# pic16f1508_breakout.net
KiCad netlist of a schematic drawn in EAGLE
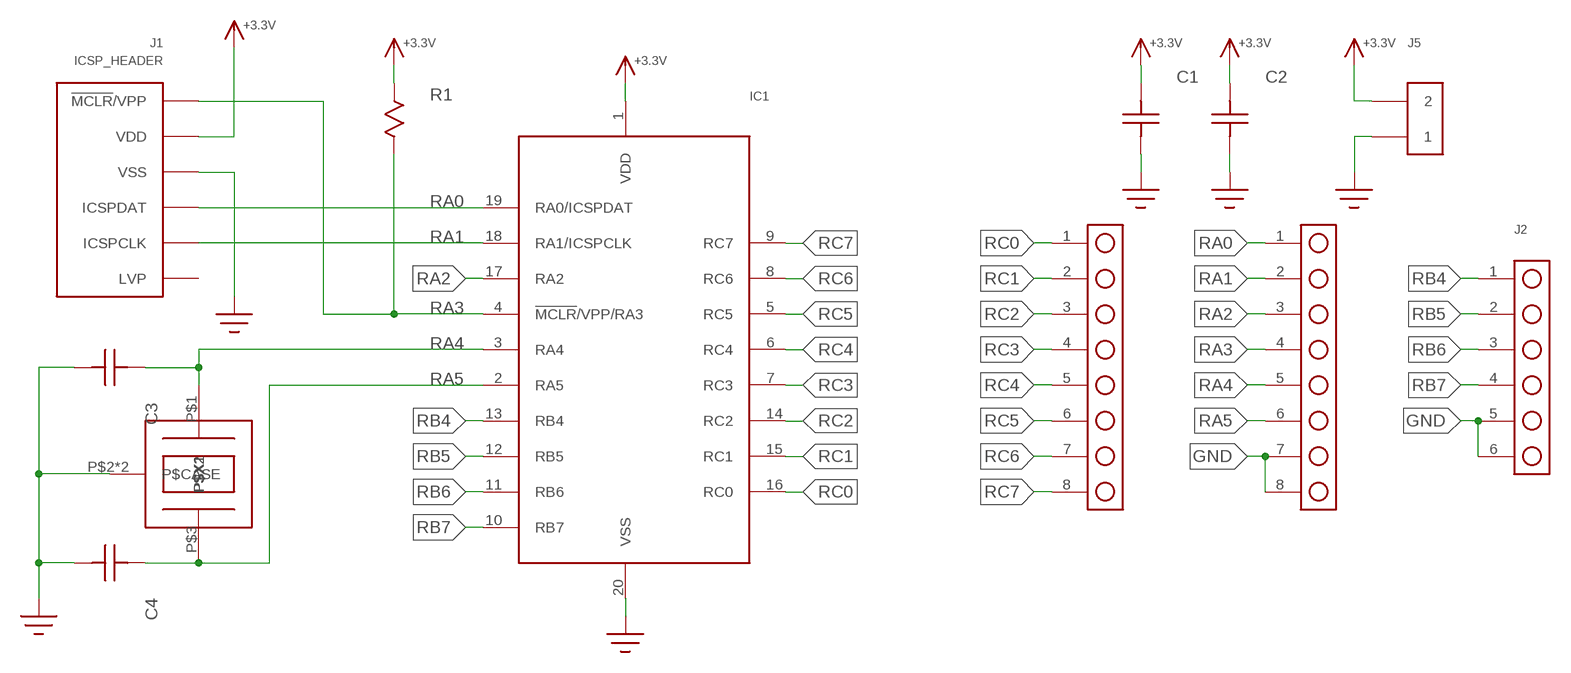
[diagram p0: schematic, sheet 1]

(export (version "E")
  (design (tool "Eeschema 10.0.6"))
  (components
    (comp (ref "C1")
      (value "C1206")
      (footprint "eagle-import:1206")
      (libsource (lib "eagle-import") (part "C1206"))
    )
    (comp (ref "C2")
      (value "C0805")
      (footprint "eagle-import:0805")
      (libsource (lib "eagle-import") (part "C0805"))
    )
    (comp (ref "C3")
      (value "C0603")
      (footprint "eagle-import:C0603")
      (libsource (lib "eagle-import") (part "C0603"))
    )
    (comp (ref "C4")
      (value "C0603")
      (footprint "eagle-import:C0603")
      (libsource (lib "eagle-import") (part "C0603"))
    )
    (comp (ref "IC1")
      (value "PIC16F1508")
      (footprint "eagle-import:20SOIC_75")
      (libsource (lib "eagle-import") (part "PIC16F1508"))
    )
    (comp (ref "J1")
      (value "ICSP_HEADER")
      (footprint "eagle-import:HEADER_6P")
      (libsource (lib "eagle-import") (part "ICSP_HEADER"))
    )
    (comp (ref "J2")
      (value "HEADER_6_PIN")
      (footprint "eagle-import:HEADER_6P")
      (libsource (lib "eagle-import") (part "HEADER_6_PIN"))
    )
    (comp (ref "J3")
      (value "HEADER_8_PIN")
      (footprint "eagle-import:HEADER_8_PIN")
      (libsource (lib "eagle-import") (part "HEADER_8_PIN"))
    )
    (comp (ref "J4")
      (value "HEADER_8_PIN")
      (footprint "eagle-import:HEADER_8_PIN")
      (libsource (lib "eagle-import") (part "HEADER_8_PIN"))
    )
    (comp (ref "J5")
      (value "HEADER_2_PIN")
      (footprint "eagle-import:HEADER_2_PIN")
      (libsource (lib "eagle-import") (part "HEADER_2_PIN"))
    )
    (comp (ref "R1")
      (value "R0805")
      (footprint "eagle-import:R0805")
      (libsource (lib "eagle-import") (part "R0805"))
    )
    (comp (ref "U$10")
      (value "XTAL")
      (footprint "eagle-import:CRYSTAL_3.2X2.5")
      (libsource (lib "eagle-import") (part "XTAL"))
    )
  )
  (nets
    (net (code "1") (name "+3.3V") (class "Default")
      (node (ref "C1") (pin "P$2") (pinfunction "P$2_P$2") (pintype "bidirectional"))
      (node (ref "C2") (pin "P$2") (pinfunction "P$2_P$2") (pintype "bidirectional"))
      (node (ref "IC1") (pin "1") (pinfunction "VDD_1") (pintype "bidirectional"))
      (node (ref "J1") (pin "2") (pinfunction "VDD_2") (pintype "bidirectional"))
      (node (ref "J5") (pin "2") (pinfunction "2_2") (pintype "bidirectional"))
      (node (ref "R1") (pin "P$1") (pinfunction "P$3_P$1") (pintype "bidirectional"))
    )
    (net (code "2") (name "GND") (class "Default")
      (node (ref "C1") (pin "P$1") (pinfunction "P$1_P$1") (pintype "bidirectional"))
      (node (ref "C2") (pin "P$1") (pinfunction "P$1_P$1") (pintype "bidirectional"))
      (node (ref "C3") (pin "P$1") (pinfunction "P$1_P$1") (pintype "bidirectional"))
      (node (ref "C4") (pin "P$1") (pinfunction "P$1_P$1") (pintype "bidirectional"))
      (node (ref "IC1") (pin "20") (pinfunction "VSS_20") (pintype "bidirectional"))
      (node (ref "J1") (pin "3") (pinfunction "VSS_3") (pintype "bidirectional"))
      (node (ref "J2") (pin "5") (pinfunction "5_5") (pintype "bidirectional"))
      (node (ref "J2") (pin "6") (pinfunction "6_6") (pintype "bidirectional"))
      (node (ref "J4") (pin "7") (pinfunction "7_7") (pintype "bidirectional"))
      (node (ref "J4") (pin "8") (pinfunction "8_8") (pintype "bidirectional"))
      (node (ref "J5") (pin "1") (pinfunction "1_1") (pintype "bidirectional"))
      (node (ref "U$10") (pin "P$2") (pinfunction "P$CASE_P$2") (pintype "bidirectional"))
      (node (ref "U$10") (pin "P$4") (pinfunction "P$CASE_P$4") (pintype "bidirectional"))
    )
    (net (code "3") (name "RA0") (class "Default")
      (node (ref "IC1") (pin "19") (pinfunction "RA0/ICSPDAT_19") (pintype "bidirectional"))
      (node (ref "J1") (pin "4") (pinfunction "ICSPDAT_4") (pintype "bidirectional"))
      (node (ref "J4") (pin "1") (pinfunction "1_1") (pintype "bidirectional"))
    )
    (net (code "4") (name "RA1") (class "Default")
      (node (ref "IC1") (pin "18") (pinfunction "RA1/ICSPCLK_18") (pintype "bidirectional"))
      (node (ref "J1") (pin "5") (pinfunction "ICSPCLK_5") (pintype "bidirectional"))
      (node (ref "J4") (pin "2") (pinfunction "2_2") (pintype "bidirectional"))
    )
    (net (code "5") (name "RA2") (class "Default")
      (node (ref "IC1") (pin "17") (pinfunction "RA2_17") (pintype "bidirectional"))
      (node (ref "J4") (pin "3") (pinfunction "3_3") (pintype "bidirectional"))
    )
    (net (code "6") (name "RA3") (class "Default")
      (node (ref "IC1") (pin "4") (pinfunction "~{MCLR}/VPP/RA3_4") (pintype "bidirectional"))
      (node (ref "J1") (pin "1") (pinfunction "~{MCLR}/VPP_1") (pintype "bidirectional"))
      (node (ref "J4") (pin "4") (pinfunction "4_4") (pintype "bidirectional"))
      (node (ref "R1") (pin "P$2") (pinfunction "P$4_P$2") (pintype "bidirectional"))
    )
    (net (code "7") (name "RA4") (class "Default")
      (node (ref "C3") (pin "P$2") (pinfunction "P$2_P$2") (pintype "bidirectional"))
      (node (ref "IC1") (pin "3") (pinfunction "RA4_3") (pintype "bidirectional"))
      (node (ref "J4") (pin "5") (pinfunction "5_5") (pintype "bidirectional"))
      (node (ref "U$10") (pin "P$1") (pinfunction "P$X1_P$1") (pintype "bidirectional"))
    )
    (net (code "8") (name "RA5") (class "Default")
      (node (ref "C4") (pin "P$2") (pinfunction "P$2_P$2") (pintype "bidirectional"))
      (node (ref "IC1") (pin "2") (pinfunction "RA5_2") (pintype "bidirectional"))
      (node (ref "J4") (pin "6") (pinfunction "6_6") (pintype "bidirectional"))
      (node (ref "U$10") (pin "P$3") (pinfunction "P$X2_P$3") (pintype "bidirectional"))
    )
    (net (code "9") (name "RB4") (class "Default")
      (node (ref "IC1") (pin "13") (pinfunction "RB4_13") (pintype "bidirectional"))
      (node (ref "J2") (pin "1") (pinfunction "1_1") (pintype "bidirectional"))
    )
    (net (code "10") (name "RB5") (class "Default")
      (node (ref "IC1") (pin "12") (pinfunction "RB5_12") (pintype "bidirectional"))
      (node (ref "J2") (pin "2") (pinfunction "2_2") (pintype "bidirectional"))
    )
    (net (code "11") (name "RB6") (class "Default")
      (node (ref "IC1") (pin "11") (pinfunction "RB6_11") (pintype "bidirectional"))
      (node (ref "J2") (pin "3") (pinfunction "3_3") (pintype "bidirectional"))
    )
    (net (code "12") (name "RB7") (class "Default")
      (node (ref "IC1") (pin "10") (pinfunction "RB7_10") (pintype "bidirectional"))
      (node (ref "J2") (pin "4") (pinfunction "4_4") (pintype "bidirectional"))
    )
    (net (code "13") (name "RC0") (class "Default")
      (node (ref "IC1") (pin "16") (pinfunction "RC0_16") (pintype "bidirectional"))
      (node (ref "J3") (pin "1") (pinfunction "1_1") (pintype "bidirectional"))
    )
    (net (code "14") (name "RC1") (class "Default")
      (node (ref "IC1") (pin "15") (pinfunction "RC1_15") (pintype "bidirectional"))
      (node (ref "J3") (pin "2") (pinfunction "2_2") (pintype "bidirectional"))
    )
    (net (code "15") (name "RC2") (class "Default")
      (node (ref "IC1") (pin "14") (pinfunction "RC2_14") (pintype "bidirectional"))
      (node (ref "J3") (pin "3") (pinfunction "3_3") (pintype "bidirectional"))
    )
    (net (code "16") (name "RC3") (class "Default")
      (node (ref "IC1") (pin "7") (pinfunction "RC3_7") (pintype "bidirectional"))
      (node (ref "J3") (pin "4") (pinfunction "4_4") (pintype "bidirectional"))
    )
    (net (code "17") (name "RC4") (class "Default")
      (node (ref "IC1") (pin "6") (pinfunction "RC4_6") (pintype "bidirectional"))
      (node (ref "J3") (pin "5") (pinfunction "5_5") (pintype "bidirectional"))
    )
    (net (code "18") (name "RC5") (class "Default")
      (node (ref "IC1") (pin "5") (pinfunction "RC5_5") (pintype "bidirectional"))
      (node (ref "J3") (pin "6") (pinfunction "6_6") (pintype "bidirectional"))
    )
    (net (code "19") (name "RC6") (class "Default")
      (node (ref "IC1") (pin "8") (pinfunction "RC6_8") (pintype "bidirectional"))
      (node (ref "J3") (pin "7") (pinfunction "7_7") (pintype "bidirectional"))
    )
    (net (code "20") (name "RC7") (class "Default")
      (node (ref "IC1") (pin "9") (pinfunction "RC7_9") (pintype "bidirectional"))
      (node (ref "J3") (pin "8") (pinfunction "8_8") (pintype "bidirectional"))
    )
    (net (code "21") (name "unconnected-(J1-LVP-Pad6)") (class "Default")
      (node (ref "J1") (pin "6") (pinfunction "LVP_6") (pintype "bidirectional"))
    )
  )
)
